# Sheet3.net
KiCad netlist of a schematic drawn in Altium Designer
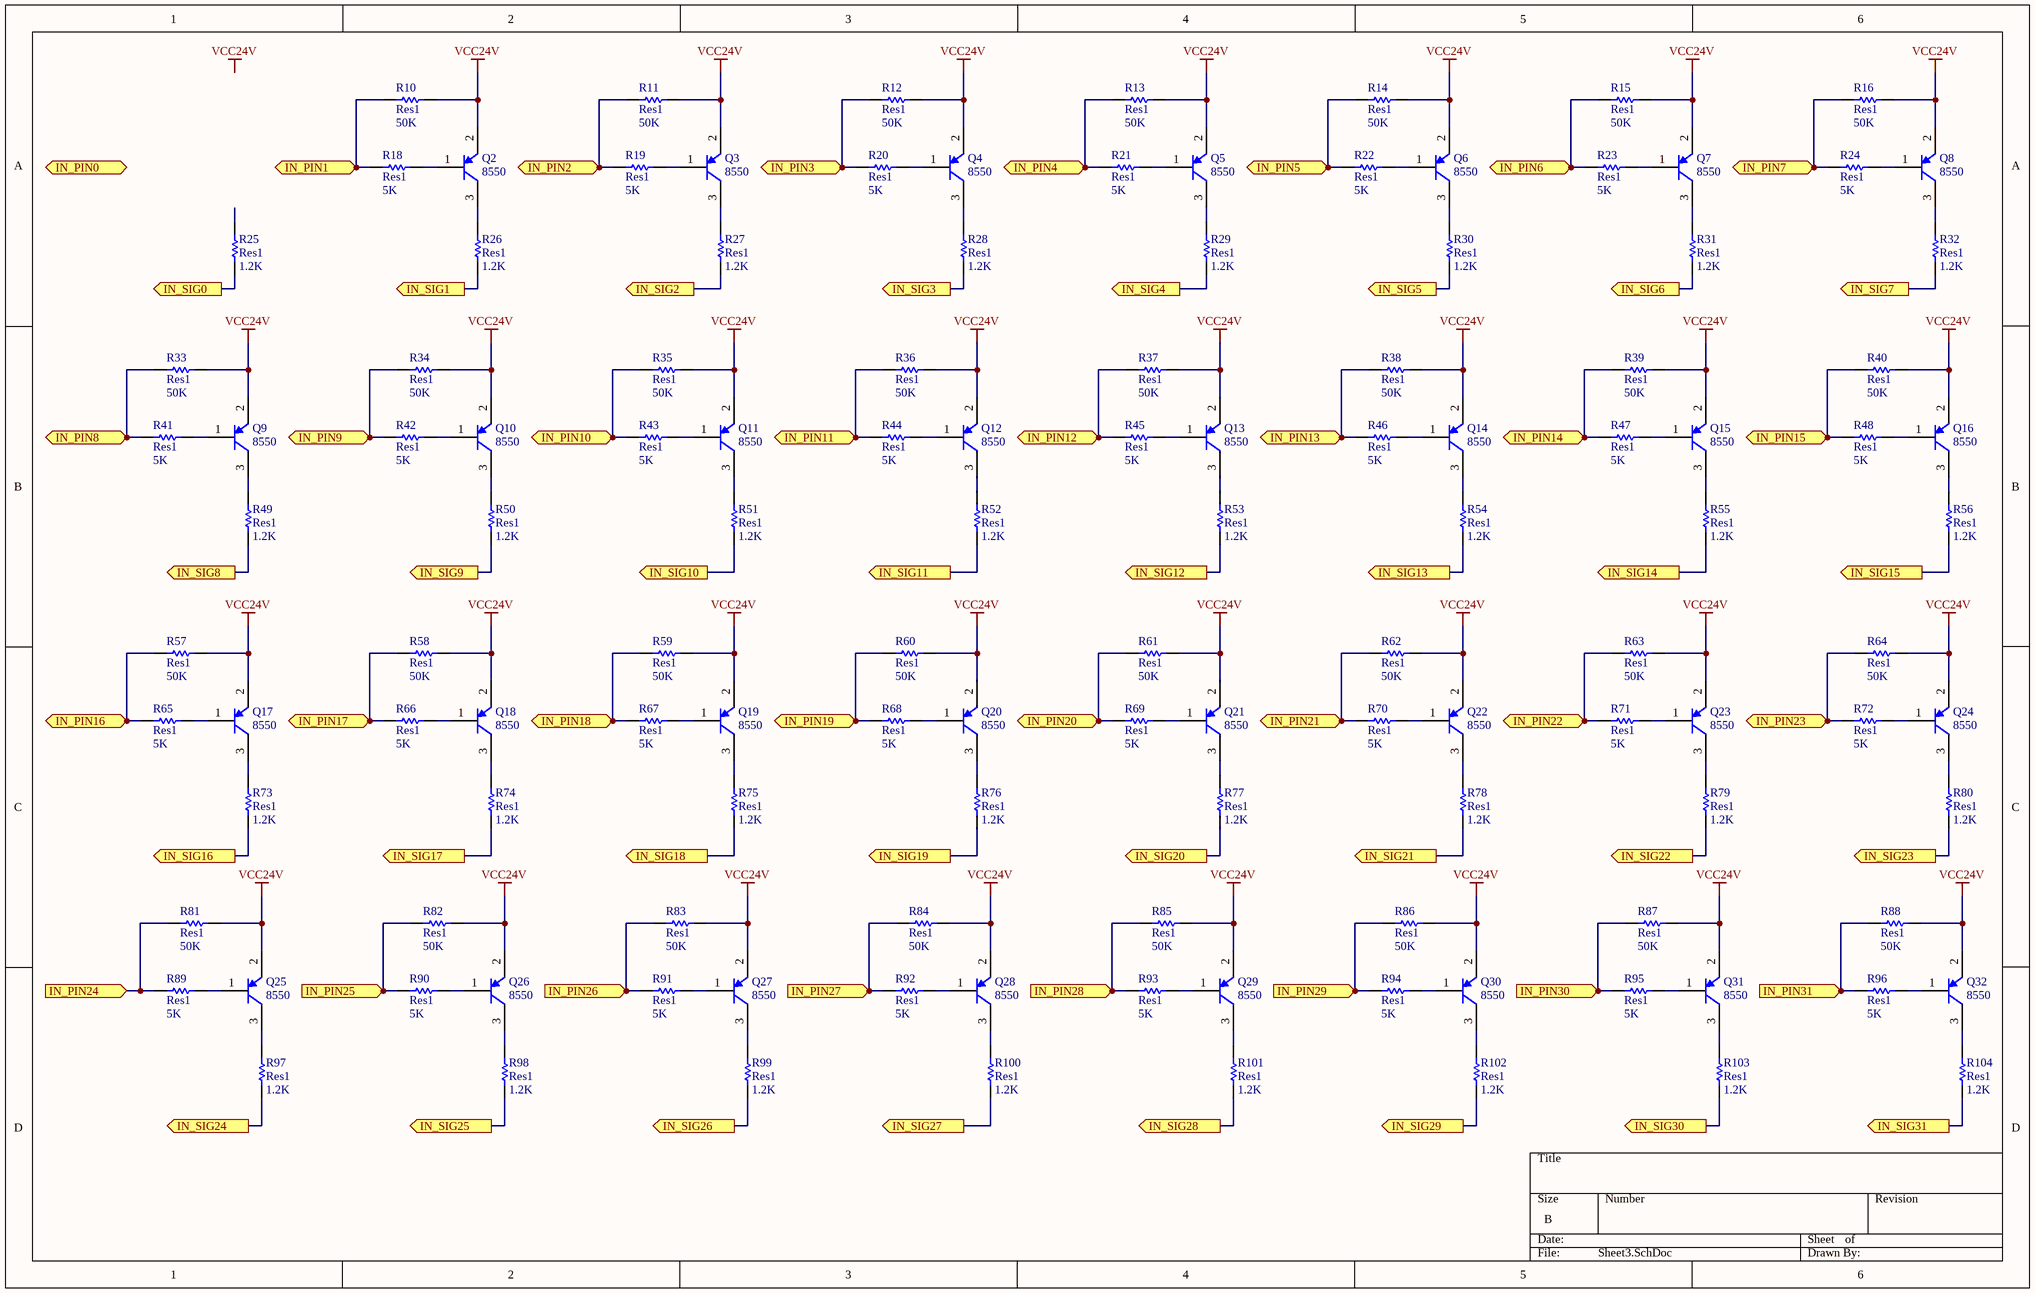
[diagram p0: Sheet3.SchDoc]

(export (version "E")
  (design (tool "Eeschema 10.0.6"))
  (components
    (comp (ref "Q2") (value "8550") (footprint "Sot23-3") (libsource (lib "dolphi_ecs") (part "PNP")))
    (comp (ref "Q3") (value "8550") (footprint "Sot23-3") (libsource (lib "dolphi_ecs") (part "PNP")))
    (comp (ref "Q4") (value "8550") (footprint "Sot23-3") (libsource (lib "dolphi_ecs") (part "PNP")))
    (comp (ref "Q5") (value "8550") (footprint "Sot23-3") (libsource (lib "dolphi_ecs") (part "PNP")))
    (comp (ref "Q6") (value "8550") (footprint "Sot23-3") (libsource (lib "dolphi_ecs") (part "PNP")))
    (comp (ref "Q7") (value "8550") (footprint "Sot23-3") (libsource (lib "dolphi_ecs") (part "PNP")))
    (comp (ref "Q8") (value "8550") (footprint "Sot23-3") (libsource (lib "dolphi_ecs") (part "PNP")))
    (comp (ref "Q9") (value "8550") (footprint "Sot23-3") (libsource (lib "dolphi_ecs") (part "PNP")))
    (comp (ref "Q10") (value "8550") (footprint "Sot23-3") (libsource (lib "dolphi_ecs") (part "PNP")))
    (comp (ref "Q11") (value "8550") (footprint "Sot23-3") (libsource (lib "dolphi_ecs") (part "PNP")))
    (comp (ref "Q12") (value "8550") (footprint "Sot23-3") (libsource (lib "dolphi_ecs") (part "PNP")))
    (comp (ref "Q13") (value "8550") (footprint "Sot23-3") (libsource (lib "dolphi_ecs") (part "PNP")))
    (comp (ref "Q14") (value "8550") (footprint "Sot23-3") (libsource (lib "dolphi_ecs") (part "PNP")))
    (comp (ref "Q15") (value "8550") (footprint "Sot23-3") (libsource (lib "dolphi_ecs") (part "PNP")))
    (comp (ref "Q16") (value "8550") (footprint "Sot23-3") (libsource (lib "dolphi_ecs") (part "PNP")))
    (comp (ref "Q17") (value "8550") (footprint "Sot23-3") (libsource (lib "dolphi_ecs") (part "PNP")))
    (comp (ref "Q18") (value "8550") (footprint "Sot23-3") (libsource (lib "dolphi_ecs") (part "PNP")))
    (comp (ref "Q19") (value "8550") (footprint "Sot23-3") (libsource (lib "dolphi_ecs") (part "PNP")))
    (comp (ref "Q20") (value "8550") (footprint "Sot23-3") (libsource (lib "dolphi_ecs") (part "PNP")))
    (comp (ref "Q21") (value "8550") (footprint "Sot23-3") (libsource (lib "dolphi_ecs") (part "PNP")))
    (comp (ref "Q22") (value "8550") (footprint "Sot23-3") (libsource (lib "dolphi_ecs") (part "PNP")))
    (comp (ref "Q23") (value "8550") (footprint "Sot23-3") (libsource (lib "dolphi_ecs") (part "PNP")))
    (comp (ref "Q24") (value "8550") (footprint "Sot23-3") (libsource (lib "dolphi_ecs") (part "PNP")))
    (comp (ref "Q25") (value "8550") (footprint "Sot23-3") (libsource (lib "dolphi_ecs") (part "PNP")))
    (comp (ref "Q26") (value "8550") (footprint "Sot23-3") (libsource (lib "dolphi_ecs") (part "PNP")))
    (comp (ref "Q27") (value "8550") (footprint "Sot23-3") (libsource (lib "dolphi_ecs") (part "PNP")))
    (comp (ref "Q28") (value "8550") (footprint "Sot23-3") (libsource (lib "dolphi_ecs") (part "PNP")))
    (comp (ref "Q29") (value "8550") (footprint "Sot23-3") (libsource (lib "dolphi_ecs") (part "PNP")))
    (comp (ref "Q30") (value "8550") (footprint "Sot23-3") (libsource (lib "dolphi_ecs") (part "PNP")))
    (comp (ref "Q31") (value "8550") (footprint "Sot23-3") (libsource (lib "dolphi_ecs") (part "PNP")))
    (comp (ref "Q32") (value "8550") (footprint "Sot23-3") (libsource (lib "dolphi_ecs") (part "PNP")))
    (comp (ref "R10")
      (value "Res1")
      (footprint "0805")
      (description "Resistor")
      (fields (field (name "ALTIUM_VALUE") "50K") (field (name "PUBLISHER") "Altium Limited"))
      (libsource (lib "Miscellaneous Devices") (part "Res1"))
    )
    (comp (ref "R11")
      (value "Res1")
      (footprint "0805")
      (description "Resistor")
      (fields (field (name "ALTIUM_VALUE") "50K") (field (name "PUBLISHER") "Altium Limited"))
      (libsource (lib "Miscellaneous Devices") (part "Res1"))
    )
    (comp (ref "R12")
      (value "Res1")
      (footprint "0805")
      (description "Resistor")
      (fields (field (name "ALTIUM_VALUE") "50K") (field (name "PUBLISHER") "Altium Limited"))
      (libsource (lib "Miscellaneous Devices") (part "Res1"))
    )
    (comp (ref "R13")
      (value "Res1")
      (footprint "0805")
      (description "Resistor")
      (fields (field (name "ALTIUM_VALUE") "50K") (field (name "PUBLISHER") "Altium Limited"))
      (libsource (lib "Miscellaneous Devices") (part "Res1"))
    )
    (comp (ref "R14")
      (value "Res1")
      (footprint "0805")
      (description "Resistor")
      (fields (field (name "ALTIUM_VALUE") "50K") (field (name "PUBLISHER") "Altium Limited"))
      (libsource (lib "Miscellaneous Devices") (part "Res1"))
    )
    (comp (ref "R15")
      (value "Res1")
      (footprint "0805")
      (description "Resistor")
      (fields (field (name "ALTIUM_VALUE") "50K") (field (name "PUBLISHER") "Altium Limited"))
      (libsource (lib "Miscellaneous Devices") (part "Res1"))
    )
    (comp (ref "R16")
      (value "Res1")
      (footprint "0805")
      (description "Resistor")
      (fields (field (name "ALTIUM_VALUE") "50K") (field (name "PUBLISHER") "Altium Limited"))
      (libsource (lib "Miscellaneous Devices") (part "Res1"))
    )
    (comp (ref "R18")
      (value "Res1")
      (footprint "0805")
      (description "Resistor")
      (fields (field (name "ALTIUM_VALUE") "5K") (field (name "PUBLISHER") "Altium Limited"))
      (libsource (lib "Miscellaneous Devices") (part "Res1"))
    )
    (comp (ref "R19")
      (value "Res1")
      (footprint "0805")
      (description "Resistor")
      (fields (field (name "ALTIUM_VALUE") "5K") (field (name "PUBLISHER") "Altium Limited"))
      (libsource (lib "Miscellaneous Devices") (part "Res1"))
    )
    (comp (ref "R20")
      (value "Res1")
      (footprint "0805")
      (description "Resistor")
      (fields (field (name "ALTIUM_VALUE") "5K") (field (name "PUBLISHER") "Altium Limited"))
      (libsource (lib "Miscellaneous Devices") (part "Res1"))
    )
    (comp (ref "R21")
      (value "Res1")
      (footprint "0805")
      (description "Resistor")
      (fields (field (name "ALTIUM_VALUE") "5K") (field (name "PUBLISHER") "Altium Limited"))
      (libsource (lib "Miscellaneous Devices") (part "Res1"))
    )
    (comp (ref "R22")
      (value "Res1")
      (footprint "0805")
      (description "Resistor")
      (fields (field (name "ALTIUM_VALUE") "5K") (field (name "PUBLISHER") "Altium Limited"))
      (libsource (lib "Miscellaneous Devices") (part "Res1"))
    )
    (comp (ref "R23")
      (value "Res1")
      (footprint "0805")
      (description "Resistor")
      (fields (field (name "ALTIUM_VALUE") "5K") (field (name "PUBLISHER") "Altium Limited"))
      (libsource (lib "Miscellaneous Devices") (part "Res1"))
    )
    (comp (ref "R24")
      (value "Res1")
      (footprint "0805")
      (description "Resistor")
      (fields (field (name "ALTIUM_VALUE") "5K") (field (name "PUBLISHER") "Altium Limited"))
      (libsource (lib "Miscellaneous Devices") (part "Res1"))
    )
    (comp (ref "R25")
      (value "Res1")
      (footprint "0805")
      (description "Resistor")
      (fields (field (name "ALTIUM_VALUE") "1.2K") (field (name "PUBLISHER") "Altium Limited"))
      (libsource (lib "Miscellaneous Devices") (part "Res1"))
    )
    (comp (ref "R26")
      (value "Res1")
      (footprint "0805")
      (description "Resistor")
      (fields (field (name "ALTIUM_VALUE") "1.2K") (field (name "PUBLISHER") "Altium Limited"))
      (libsource (lib "Miscellaneous Devices") (part "Res1"))
    )
    (comp (ref "R27")
      (value "Res1")
      (footprint "0805")
      (description "Resistor")
      (fields (field (name "ALTIUM_VALUE") "1.2K") (field (name "PUBLISHER") "Altium Limited"))
      (libsource (lib "Miscellaneous Devices") (part "Res1"))
    )
    (comp (ref "R28")
      (value "Res1")
      (footprint "0805")
      (description "Resistor")
      (fields (field (name "ALTIUM_VALUE") "1.2K") (field (name "PUBLISHER") "Altium Limited"))
      (libsource (lib "Miscellaneous Devices") (part "Res1"))
    )
    (comp (ref "R29")
      (value "Res1")
      (footprint "0805")
      (description "Resistor")
      (fields (field (name "ALTIUM_VALUE") "1.2K") (field (name "PUBLISHER") "Altium Limited"))
      (libsource (lib "Miscellaneous Devices") (part "Res1"))
    )
    (comp (ref "R30")
      (value "Res1")
      (footprint "0805")
      (description "Resistor")
      (fields (field (name "ALTIUM_VALUE") "1.2K") (field (name "PUBLISHER") "Altium Limited"))
      (libsource (lib "Miscellaneous Devices") (part "Res1"))
    )
    (comp (ref "R31")
      (value "Res1")
      (footprint "0805")
      (description "Resistor")
      (fields (field (name "ALTIUM_VALUE") "1.2K") (field (name "PUBLISHER") "Altium Limited"))
      (libsource (lib "Miscellaneous Devices") (part "Res1"))
    )
    (comp (ref "R32")
      (value "Res1")
      (footprint "0805")
      (description "Resistor")
      (fields (field (name "ALTIUM_VALUE") "1.2K") (field (name "PUBLISHER") "Altium Limited"))
      (libsource (lib "Miscellaneous Devices") (part "Res1"))
    )
    (comp (ref "R33")
      (value "Res1")
      (footprint "0805")
      (description "Resistor")
      (fields (field (name "ALTIUM_VALUE") "50K") (field (name "PUBLISHER") "Altium Limited"))
      (libsource (lib "Miscellaneous Devices") (part "Res1"))
    )
    (comp (ref "R34")
      (value "Res1")
      (footprint "0805")
      (description "Resistor")
      (fields (field (name "ALTIUM_VALUE") "50K") (field (name "PUBLISHER") "Altium Limited"))
      (libsource (lib "Miscellaneous Devices") (part "Res1"))
    )
    (comp (ref "R35")
      (value "Res1")
      (footprint "0805")
      (description "Resistor")
      (fields (field (name "ALTIUM_VALUE") "50K") (field (name "PUBLISHER") "Altium Limited"))
      (libsource (lib "Miscellaneous Devices") (part "Res1"))
    )
    (comp (ref "R36")
      (value "Res1")
      (footprint "0805")
      (description "Resistor")
      (fields (field (name "ALTIUM_VALUE") "50K") (field (name "PUBLISHER") "Altium Limited"))
      (libsource (lib "Miscellaneous Devices") (part "Res1"))
    )
    (comp (ref "R37")
      (value "Res1")
      (footprint "0805")
      (description "Resistor")
      (fields (field (name "ALTIUM_VALUE") "50K") (field (name "PUBLISHER") "Altium Limited"))
      (libsource (lib "Miscellaneous Devices") (part "Res1"))
    )
    (comp (ref "R38")
      (value "Res1")
      (footprint "0805")
      (description "Resistor")
      (fields (field (name "ALTIUM_VALUE") "50K") (field (name "PUBLISHER") "Altium Limited"))
      (libsource (lib "Miscellaneous Devices") (part "Res1"))
    )
    (comp (ref "R39")
      (value "Res1")
      (footprint "0805")
      (description "Resistor")
      (fields (field (name "ALTIUM_VALUE") "50K") (field (name "PUBLISHER") "Altium Limited"))
      (libsource (lib "Miscellaneous Devices") (part "Res1"))
    )
    (comp (ref "R40")
      (value "Res1")
      (footprint "0805")
      (description "Resistor")
      (fields (field (name "ALTIUM_VALUE") "50K") (field (name "PUBLISHER") "Altium Limited"))
      (libsource (lib "Miscellaneous Devices") (part "Res1"))
    )
    (comp (ref "R41")
      (value "Res1")
      (footprint "0805")
      (description "Resistor")
      (fields (field (name "ALTIUM_VALUE") "5K") (field (name "PUBLISHER") "Altium Limited"))
      (libsource (lib "Miscellaneous Devices") (part "Res1"))
    )
    (comp (ref "R42")
      (value "Res1")
      (footprint "0805")
      (description "Resistor")
      (fields (field (name "ALTIUM_VALUE") "5K") (field (name "PUBLISHER") "Altium Limited"))
      (libsource (lib "Miscellaneous Devices") (part "Res1"))
    )
    (comp (ref "R43")
      (value "Res1")
      (footprint "0805")
      (description "Resistor")
      (fields (field (name "ALTIUM_VALUE") "5K") (field (name "PUBLISHER") "Altium Limited"))
      (libsource (lib "Miscellaneous Devices") (part "Res1"))
    )
    (comp (ref "R44")
      (value "Res1")
      (footprint "0805")
      (description "Resistor")
      (fields (field (name "ALTIUM_VALUE") "5K") (field (name "PUBLISHER") "Altium Limited"))
      (libsource (lib "Miscellaneous Devices") (part "Res1"))
    )
    (comp (ref "R45")
      (value "Res1")
      (footprint "0805")
      (description "Resistor")
      (fields (field (name "ALTIUM_VALUE") "5K") (field (name "PUBLISHER") "Altium Limited"))
      (libsource (lib "Miscellaneous Devices") (part "Res1"))
    )
    (comp (ref "R46")
      (value "Res1")
      (footprint "0805")
      (description "Resistor")
      (fields (field (name "ALTIUM_VALUE") "5K") (field (name "PUBLISHER") "Altium Limited"))
      (libsource (lib "Miscellaneous Devices") (part "Res1"))
    )
    (comp (ref "R47")
      (value "Res1")
      (footprint "0805")
      (description "Resistor")
      (fields (field (name "ALTIUM_VALUE") "5K") (field (name "PUBLISHER") "Altium Limited"))
      (libsource (lib "Miscellaneous Devices") (part "Res1"))
    )
    (comp (ref "R48")
      (value "Res1")
      (footprint "0805")
      (description "Resistor")
      (fields (field (name "ALTIUM_VALUE") "5K") (field (name "PUBLISHER") "Altium Limited"))
      (libsource (lib "Miscellaneous Devices") (part "Res1"))
    )
    (comp (ref "R49")
      (value "Res1")
      (footprint "0805")
      (description "Resistor")
      (fields (field (name "ALTIUM_VALUE") "1.2K") (field (name "PUBLISHER") "Altium Limited"))
      (libsource (lib "Miscellaneous Devices") (part "Res1"))
    )
    (comp (ref "R50")
      (value "Res1")
      (footprint "0805")
      (description "Resistor")
      (fields (field (name "ALTIUM_VALUE") "1.2K") (field (name "PUBLISHER") "Altium Limited"))
      (libsource (lib "Miscellaneous Devices") (part "Res1"))
    )
    (comp (ref "R51")
      (value "Res1")
      (footprint "0805")
      (description "Resistor")
      (fields (field (name "ALTIUM_VALUE") "1.2K") (field (name "PUBLISHER") "Altium Limited"))
      (libsource (lib "Miscellaneous Devices") (part "Res1"))
    )
    (comp (ref "R52")
      (value "Res1")
      (footprint "0805")
      (description "Resistor")
      (fields (field (name "ALTIUM_VALUE") "1.2K") (field (name "PUBLISHER") "Altium Limited"))
      (libsource (lib "Miscellaneous Devices") (part "Res1"))
    )
    (comp (ref "R53")
      (value "Res1")
      (footprint "0805")
      (description "Resistor")
      (fields (field (name "ALTIUM_VALUE") "1.2K") (field (name "PUBLISHER") "Altium Limited"))
      (libsource (lib "Miscellaneous Devices") (part "Res1"))
    )
    (comp (ref "R54")
      (value "Res1")
      (footprint "0805")
      (description "Resistor")
      (fields (field (name "ALTIUM_VALUE") "1.2K") (field (name "PUBLISHER") "Altium Limited"))
      (libsource (lib "Miscellaneous Devices") (part "Res1"))
    )
    (comp (ref "R55")
      (value "Res1")
      (footprint "0805")
      (description "Resistor")
      (fields (field (name "ALTIUM_VALUE") "1.2K") (field (name "PUBLISHER") "Altium Limited"))
      (libsource (lib "Miscellaneous Devices") (part "Res1"))
    )
    (comp (ref "R56")
      (value "Res1")
      (footprint "0805")
      (description "Resistor")
      (fields (field (name "ALTIUM_VALUE") "1.2K") (field (name "PUBLISHER") "Altium Limited"))
      (libsource (lib "Miscellaneous Devices") (part "Res1"))
    )
    (comp (ref "R57")
      (value "Res1")
      (footprint "0805")
      (description "Resistor")
      (fields (field (name "ALTIUM_VALUE") "50K") (field (name "PUBLISHER") "Altium Limited"))
      (libsource (lib "Miscellaneous Devices") (part "Res1"))
    )
    (comp (ref "R58")
      (value "Res1")
      (footprint "0805")
      (description "Resistor")
      (fields (field (name "ALTIUM_VALUE") "50K") (field (name "PUBLISHER") "Altium Limited"))
      (libsource (lib "Miscellaneous Devices") (part "Res1"))
    )
    (comp (ref "R59")
      (value "Res1")
      (footprint "0805")
      (description "Resistor")
      (fields (field (name "ALTIUM_VALUE") "50K") (field (name "PUBLISHER") "Altium Limited"))
      (libsource (lib "Miscellaneous Devices") (part "Res1"))
    )
    (comp (ref "R60")
      (value "Res1")
      (footprint "0805")
      (description "Resistor")
      (fields (field (name "ALTIUM_VALUE") "50K") (field (name "PUBLISHER") "Altium Limited"))
      (libsource (lib "Miscellaneous Devices") (part "Res1"))
    )
    (comp (ref "R61")
      (value "Res1")
      (footprint "0805")
      (description "Resistor")
      (fields (field (name "ALTIUM_VALUE") "50K") (field (name "PUBLISHER") "Altium Limited"))
      (libsource (lib "Miscellaneous Devices") (part "Res1"))
    )
    (comp (ref "R62")
      (value "Res1")
      (footprint "0805")
      (description "Resistor")
      (fields (field (name "ALTIUM_VALUE") "50K") (field (name "PUBLISHER") "Altium Limited"))
      (libsource (lib "Miscellaneous Devices") (part "Res1"))
    )
    (comp (ref "R63")
      (value "Res1")
      (footprint "0805")
      (description "Resistor")
      (fields (field (name "ALTIUM_VALUE") "50K") (field (name "PUBLISHER") "Altium Limited"))
      (libsource (lib "Miscellaneous Devices") (part "Res1"))
    )
    (comp (ref "R64")
      (value "Res1")
      (footprint "0805")
      (description "Resistor")
      (fields (field (name "ALTIUM_VALUE") "50K") (field (name "PUBLISHER") "Altium Limited"))
      (libsource (lib "Miscellaneous Devices") (part "Res1"))
    )
    (comp (ref "R65")
      (value "Res1")
      (footprint "0805")
      (description "Resistor")
      (fields (field (name "ALTIUM_VALUE") "5K") (field (name "PUBLISHER") "Altium Limited"))
      (libsource (lib "Miscellaneous Devices") (part "Res1"))
    )
    (comp (ref "R66")
      (value "Res1")
      (footprint "0805")
      (description "Resistor")
      (fields (field (name "ALTIUM_VALUE") "5K") (field (name "PUBLISHER") "Altium Limited"))
      (libsource (lib "Miscellaneous Devices") (part "Res1"))
    )
    (comp (ref "R67")
      (value "Res1")
      (footprint "0805")
      (description "Resistor")
      (fields (field (name "ALTIUM_VALUE") "5K") (field (name "PUBLISHER") "Altium Limited"))
      (libsource (lib "Miscellaneous Devices") (part "Res1"))
    )
    (comp (ref "R68")
      (value "Res1")
      (footprint "0805")
      (description "Resistor")
      (fields (field (name "ALTIUM_VALUE") "5K") (field (name "PUBLISHER") "Altium Limited"))
      (libsource (lib "Miscellaneous Devices") (part "Res1"))
    )
    (comp (ref "R69")
      (value "Res1")
      (footprint "0805")
      (description "Resistor")
      (fields (field (name "ALTIUM_VALUE") "5K") (field (name "PUBLISHER") "Altium Limited"))
      (libsource (lib "Miscellaneous Devices") (part "Res1"))
    )
    (comp (ref "R70")
      (value "Res1")
      (footprint "0805")
      (description "Resistor")
      (fields (field (name "ALTIUM_VALUE") "5K") (field (name "PUBLISHER") "Altium Limited"))
      (libsource (lib "Miscellaneous Devices") (part "Res1"))
    )
    (comp (ref "R71")
      (value "Res1")
      (footprint "0805")
      (description "Resistor")
      (fields (field (name "ALTIUM_VALUE") "5K") (field (name "PUBLISHER") "Altium Limited"))
      (libsource (lib "Miscellaneous Devices") (part "Res1"))
    )
    (comp (ref "R72")
      (value "Res1")
      (footprint "0805")
      (description "Resistor")
      (fields (field (name "ALTIUM_VALUE") "5K") (field (name "PUBLISHER") "Altium Limited"))
      (libsource (lib "Miscellaneous Devices") (part "Res1"))
    )
    (comp (ref "R73")
      (value "Res1")
      (footprint "0805")
      (description "Resistor")
      (fields (field (name "ALTIUM_VALUE") "1.2K") (field (name "PUBLISHER") "Altium Limited"))
      (libsource (lib "Miscellaneous Devices") (part "Res1"))
    )
    (comp (ref "R74")
      (value "Res1")
      (footprint "0805")
      (description "Resistor")
      (fields (field (name "ALTIUM_VALUE") "1.2K") (field (name "PUBLISHER") "Altium Limited"))
      (libsource (lib "Miscellaneous Devices") (part "Res1"))
    )
    (comp (ref "R75")
      (value "Res1")
      (footprint "0805")
      (description "Resistor")
      (fields (field (name "ALTIUM_VALUE") "1.2K") (field (name "PUBLISHER") "Altium Limited"))
      (libsource (lib "Miscellaneous Devices") (part "Res1"))
    )
    (comp (ref "R76")
      (value "Res1")
      (footprint "0805")
      (description "Resistor")
      (fields (field (name "ALTIUM_VALUE") "1.2K") (field (name "PUBLISHER") "Altium Limited"))
      (libsource (lib "Miscellaneous Devices") (part "Res1"))
    )
    (comp (ref "R77")
      (value "Res1")
      (footprint "0805")
      (description "Resistor")
      (fields (field (name "ALTIUM_VALUE") "1.2K") (field (name "PUBLISHER") "Altium Limited"))
      (libsource (lib "Miscellaneous Devices") (part "Res1"))
    )
    (comp (ref "R78")
      (value "Res1")
      (footprint "0805")
      (description "Resistor")
      (fields (field (name "ALTIUM_VALUE") "1.2K") (field (name "PUBLISHER") "Altium Limited"))
      (libsource (lib "Miscellaneous Devices") (part "Res1"))
    )
    (comp (ref "R79")
      (value "Res1")
      (footprint "0805")
      (description "Resistor")
      (fields (field (name "ALTIUM_VALUE") "1.2K") (field (name "PUBLISHER") "Altium Limited"))
      (libsource (lib "Miscellaneous Devices") (part "Res1"))
    )
    (comp (ref "R80")
      (value "Res1")
      (footprint "0805")
      (description "Resistor")
      (fields (field (name "ALTIUM_VALUE") "1.2K") (field (name "PUBLISHER") "Altium Limited"))
      (libsource (lib "Miscellaneous Devices") (part "Res1"))
    )
    (comp (ref "R81")
      (value "Res1")
      (footprint "0805")
      (description "Resistor")
      (fields (field (name "ALTIUM_VALUE") "50K") (field (name "PUBLISHER") "Altium Limited"))
      (libsource (lib "Miscellaneous Devices") (part "Res1"))
    )
    (comp (ref "R82")
      (value "Res1")
      (footprint "0805")
      (description "Resistor")
      (fields (field (name "ALTIUM_VALUE") "50K") (field (name "PUBLISHER") "Altium Limited"))
      (libsource (lib "Miscellaneous Devices") (part "Res1"))
    )
    (comp (ref "R83")
      (value "Res1")
      (footprint "0805")
      (description "Resistor")
      (fields (field (name "ALTIUM_VALUE") "50K") (field (name "PUBLISHER") "Altium Limited"))
      (libsource (lib "Miscellaneous Devices") (part "Res1"))
    )
    (comp (ref "R84")
      (value "Res1")
      (footprint "0805")
      (description "Resistor")
      (fields (field (name "ALTIUM_VALUE") "50K") (field (name "PUBLISHER") "Altium Limited"))
      (libsource (lib "Miscellaneous Devices") (part "Res1"))
    )
    (comp (ref "R85")
      (value "Res1")
      (footprint "0805")
      (description "Resistor")
      (fields (field (name "ALTIUM_VALUE") "50K") (field (name "PUBLISHER") "Altium Limited"))
      (libsource (lib "Miscellaneous Devices") (part "Res1"))
    )
    (comp (ref "R86")
      (value "Res1")
      (footprint "0805")
      (description "Resistor")
      (fields (field (name "ALTIUM_VALUE") "50K") (field (name "PUBLISHER") "Altium Limited"))
      (libsource (lib "Miscellaneous Devices") (part "Res1"))
    )
    (comp (ref "R87")
      (value "Res1")
      (footprint "0805")
      (description "Resistor")
      (fields (field (name "ALTIUM_VALUE") "50K") (field (name "PUBLISHER") "Altium Limited"))
      (libsource (lib "Miscellaneous Devices") (part "Res1"))
    )
    (comp (ref "R88")
      (value "Res1")
      (footprint "0805")
      (description "Resistor")
      (fields (field (name "ALTIUM_VALUE") "50K") (field (name "PUBLISHER") "Altium Limited"))
      (libsource (lib "Miscellaneous Devices") (part "Res1"))
    )
    (comp (ref "R89")
      (value "Res1")
      (footprint "0805")
      (description "Resistor")
      (fields (field (name "ALTIUM_VALUE") "5K") (field (name "PUBLISHER") "Altium Limited"))
      (libsource (lib "Miscellaneous Devices") (part "Res1"))
    )
    (comp (ref "R90")
      (value "Res1")
      (footprint "0805")
      (description "Resistor")
      (fields (field (name "ALTIUM_VALUE") "5K") (field (name "PUBLISHER") "Altium Limited"))
      (libsource (lib "Miscellaneous Devices") (part "Res1"))
    )
    (comp (ref "R91")
      (value "Res1")
      (footprint "0805")
      (description "Resistor")
      (fields (field (name "ALTIUM_VALUE") "5K") (field (name "PUBLISHER") "Altium Limited"))
      (libsource (lib "Miscellaneous Devices") (part "Res1"))
    )
    (comp (ref "R92")
      (value "Res1")
      (footprint "0805")
      (description "Resistor")
      (fields (field (name "ALTIUM_VALUE") "5K") (field (name "PUBLISHER") "Altium Limited"))
      (libsource (lib "Miscellaneous Devices") (part "Res1"))
    )
    (comp (ref "R93")
      (value "Res1")
      (footprint "0805")
      (description "Resistor")
      (fields (field (name "ALTIUM_VALUE") "5K") (field (name "PUBLISHER") "Altium Limited"))
      (libsource (lib "Miscellaneous Devices") (part "Res1"))
    )
    (comp (ref "R94")
      (value "Res1")
      (footprint "0805")
      (description "Resistor")
      (fields (field (name "ALTIUM_VALUE") "5K") (field (name "PUBLISHER") "Altium Limited"))
      (libsource (lib "Miscellaneous Devices") (part "Res1"))
    )
    (comp (ref "R95")
      (value "Res1")
      (footprint "0805")
      (description "Resistor")
      (fields (field (name "ALTIUM_VALUE") "5K") (field (name "PUBLISHER") "Altium Limited"))
      (libsource (lib "Miscellaneous Devices") (part "Res1"))
    )
    (comp (ref "R96")
      (value "Res1")
      (footprint "0805")
      (description "Resistor")
      (fields (field (name "ALTIUM_VALUE") "5K") (field (name "PUBLISHER") "Altium Limited"))
      (libsource (lib "Miscellaneous Devices") (part "Res1"))
    )
    (comp (ref "R97")
      (value "Res1")
      (footprint "0805")
      (description "Resistor")
      (fields (field (name "ALTIUM_VALUE") "1.2K") (field (name "PUBLISHER") "Altium Limited"))
      (libsource (lib "Miscellaneous Devices") (part "Res1"))
    )
    (comp (ref "R98")
      (value "Res1")
      (footprint "0805")
      (description "Resistor")
      (fields (field (name "ALTIUM_VALUE") "1.2K") (field (name "PUBLISHER") "Altium Limited"))
      (libsource (lib "Miscellaneous Devices") (part "Res1"))
    )
    (comp (ref "R99")
      (value "Res1")
      (footprint "0805")
      (description "Resistor")
      (fields (field (name "ALTIUM_VALUE") "1.2K") (field (name "PUBLISHER") "Altium Limited"))
      (libsource (lib "Miscellaneous Devices") (part "Res1"))
    )
    (comp (ref "R100")
      (value "Res1")
      (footprint "0805")
      (description "Resistor")
      (fields (field (name "ALTIUM_VALUE") "1.2K") (field (name "PUBLISHER") "Altium Limited"))
      (libsource (lib "Miscellaneous Devices") (part "Res1"))
    )
    (comp (ref "R101")
      (value "Res1")
      (footprint "0805")
      (description "Resistor")
      (fields (field (name "ALTIUM_VALUE") "1.2K") (field (name "PUBLISHER") "Altium Limited"))
      (libsource (lib "Miscellaneous Devices") (part "Res1"))
    )
    (comp (ref "R102")
      (value "Res1")
      (footprint "0805")
      (description "Resistor")
      (fields (field (name "ALTIUM_VALUE") "1.2K") (field (name "PUBLISHER") "Altium Limited"))
      (libsource (lib "Miscellaneous Devices") (part "Res1"))
    )
    (comp (ref "R103")
      (value "Res1")
      (footprint "0805")
      (description "Resistor")
      (fields (field (name "ALTIUM_VALUE") "1.2K") (field (name "PUBLISHER") "Altium Limited"))
      (libsource (lib "Miscellaneous Devices") (part "Res1"))
    )
    (comp (ref "R104")
      (value "Res1")
      (footprint "0805")
      (description "Resistor")
      (fields (field (name "ALTIUM_VALUE") "1.2K") (field (name "PUBLISHER") "Altium Limited"))
      (libsource (lib "Miscellaneous Devices") (part "Res1"))
    )
  )
  (nets
    (net (code "2") (name "/IN_PIN1") (class "Default")
      (node (ref "R10") (pin "2") (pinfunction "2_2") (pintype "passive"))
      (node (ref "R18") (pin "1") (pinfunction "1_1") (pintype "passive"))
    )
    (net (code "3") (name "/IN_PIN2") (class "Default")
      (node (ref "R11") (pin "2") (pinfunction "2_2") (pintype "passive"))
      (node (ref "R19") (pin "1") (pinfunction "1_1") (pintype "passive"))
    )
    (net (code "4") (name "/IN_PIN3") (class "Default")
      (node (ref "R12") (pin "2") (pinfunction "2_2") (pintype "passive"))
      (node (ref "R20") (pin "1") (pinfunction "1_1") (pintype "passive"))
    )
    (net (code "5") (name "/IN_PIN4") (class "Default")
      (node (ref "R13") (pin "2") (pinfunction "2_2") (pintype "passive"))
      (node (ref "R21") (pin "1") (pinfunction "1_1") (pintype "passive"))
    )
    (net (code "6") (name "/IN_PIN5") (class "Default")
      (node (ref "R14") (pin "2") (pinfunction "2_2") (pintype "passive"))
      (node (ref "R22") (pin "1") (pinfunction "1_1") (pintype "passive"))
    )
    (net (code "7") (name "/IN_PIN6") (class "Default")
      (node (ref "R15") (pin "2") (pinfunction "2_2") (pintype "passive"))
      (node (ref "R23") (pin "1") (pinfunction "1_1") (pintype "passive"))
    )
    (net (code "8") (name "/IN_PIN7") (class "Default")
      (node (ref "R16") (pin "2") (pinfunction "2_2") (pintype "passive"))
      (node (ref "R24") (pin "1") (pinfunction "1_1") (pintype "passive"))
    )
    (net (code "9") (name "/IN_PIN8") (class "Default")
      (node (ref "R33") (pin "2") (pinfunction "2_2") (pintype "passive"))
      (node (ref "R41") (pin "1") (pinfunction "1_1") (pintype "passive"))
    )
    (net (code "10") (name "/IN_PIN9") (class "Default")
      (node (ref "R34") (pin "2") (pinfunction "2_2") (pintype "passive"))
      (node (ref "R42") (pin "1") (pinfunction "1_1") (pintype "passive"))
    )
    (net (code "11") (name "/IN_PIN10") (class "Default")
      (node (ref "R35") (pin "2") (pinfunction "2_2") (pintype "passive"))
      (node (ref "R43") (pin "1") (pinfunction "1_1") (pintype "passive"))
    )
    (net (code "12") (name "/IN_PIN11") (class "Default")
      (node (ref "R36") (pin "2") (pinfunction "2_2") (pintype "passive"))
      (node (ref "R44") (pin "1") (pinfunction "1_1") (pintype "passive"))
    )
    (net (code "13") (name "/IN_PIN12") (class "Default")
      (node (ref "R37") (pin "2") (pinfunction "2_2") (pintype "passive"))
      (node (ref "R45") (pin "1") (pinfunction "1_1") (pintype "passive"))
    )
    (net (code "14") (name "/IN_PIN13") (class "Default")
      (node (ref "R38") (pin "2") (pinfunction "2_2") (pintype "passive"))
      (node (ref "R46") (pin "1") (pinfunction "1_1") (pintype "passive"))
    )
    (net (code "15") (name "/IN_PIN14") (class "Default")
      (node (ref "R39") (pin "2") (pinfunction "2_2") (pintype "passive"))
      (node (ref "R47") (pin "1") (pinfunction "1_1") (pintype "passive"))
    )
    (net (code "16") (name "/IN_PIN15") (class "Default")
      (node (ref "R40") (pin "2") (pinfunction "2_2") (pintype "passive"))
      (node (ref "R48") (pin "1") (pinfunction "1_1") (pintype "passive"))
    )
    (net (code "17") (name "/IN_PIN16") (class "Default")
      (node (ref "R57") (pin "2") (pinfunction "2_2") (pintype "passive"))
      (node (ref "R65") (pin "1") (pinfunction "1_1") (pintype "passive"))
    )
    (net (code "18") (name "/IN_PIN17") (class "Default")
      (node (ref "R58") (pin "2") (pinfunction "2_2") (pintype "passive"))
      (node (ref "R66") (pin "1") (pinfunction "1_1") (pintype "passive"))
    )
    (net (code "19") (name "/IN_PIN18") (class "Default")
      (node (ref "R59") (pin "2") (pinfunction "2_2") (pintype "passive"))
      (node (ref "R67") (pin "1") (pinfunction "1_1") (pintype "passive"))
    )
    (net (code "20") (name "/IN_PIN19") (class "Default")
      (node (ref "R60") (pin "2") (pinfunction "2_2") (pintype "passive"))
      (node (ref "R68") (pin "1") (pinfunction "1_1") (pintype "passive"))
    )
    (net (code "21") (name "/IN_PIN20") (class "Default")
      (node (ref "R61") (pin "2") (pinfunction "2_2") (pintype "passive"))
      (node (ref "R69") (pin "1") (pinfunction "1_1") (pintype "passive"))
    )
    (net (code "22") (name "/IN_PIN21") (class "Default")
      (node (ref "R62") (pin "2") (pinfunction "2_2") (pintype "passive"))
      (node (ref "R70") (pin "1") (pinfunction "1_1") (pintype "passive"))
    )
    (net (code "23") (name "/IN_PIN22") (class "Default")
      (node (ref "R63") (pin "2") (pinfunction "2_2") (pintype "passive"))
      (node (ref "R71") (pin "1") (pinfunction "1_1") (pintype "passive"))
    )
    (net (code "24") (name "/IN_PIN23") (class "Default")
      (node (ref "R64") (pin "2") (pinfunction "2_2") (pintype "passive"))
      (node (ref "R72") (pin "1") (pinfunction "1_1") (pintype "passive"))
    )
    (net (code "25") (name "/IN_PIN24") (class "Default")
      (node (ref "R81") (pin "2") (pinfunction "2_2") (pintype "passive"))
      (node (ref "R89") (pin "1") (pinfunction "1_1") (pintype "passive"))
    )
    (net (code "26") (name "/IN_PIN25") (class "Default")
      (node (ref "R82") (pin "2") (pinfunction "2_2") (pintype "passive"))
      (node (ref "R90") (pin "1") (pinfunction "1_1") (pintype "passive"))
    )
    (net (code "27") (name "/IN_PIN26") (class "Default")
      (node (ref "R83") (pin "2") (pinfunction "2_2") (pintype "passive"))
      (node (ref "R91") (pin "1") (pinfunction "1_1") (pintype "passive"))
    )
    (net (code "28") (name "/IN_PIN27") (class "Default")
      (node (ref "R84") (pin "2") (pinfunction "2_2") (pintype "passive"))
      (node (ref "R92") (pin "1") (pinfunction "1_1") (pintype "passive"))
    )
    (net (code "29") (name "/IN_PIN28") (class "Default")
      (node (ref "R85") (pin "2") (pinfunction "2_2") (pintype "passive"))
      (node (ref "R93") (pin "1") (pinfunction "1_1") (pintype "passive"))
    )
    (net (code "30") (name "/IN_PIN29") (class "Default")
      (node (ref "R86") (pin "2") (pinfunction "2_2") (pintype "passive"))
      (node (ref "R94") (pin "1") (pinfunction "1_1") (pintype "passive"))
    )
    (net (code "31") (name "/IN_PIN30") (class "Default")
      (node (ref "R87") (pin "2") (pinfunction "2_2") (pintype "passive"))
      (node (ref "R95") (pin "1") (pinfunction "1_1") (pintype "passive"))
    )
    (net (code "32") (name "/IN_PIN31") (class "Default")
      (node (ref "R88") (pin "2") (pinfunction "2_2") (pintype "passive"))
      (node (ref "R96") (pin "1") (pinfunction "1_1") (pintype "passive"))
    )
    (net (code "33") (name "/IN_SIG0") (class "Default")
      (node (ref "R25") (pin "2") (pinfunction "2_2") (pintype "passive"))
    )
    (net (code "34") (name "/IN_SIG1") (class "Default")
      (node (ref "R26") (pin "2") (pinfunction "2_2") (pintype "passive"))
    )
    (net (code "35") (name "/IN_SIG2") (class "Default")
      (node (ref "R27") (pin "2") (pinfunction "2_2") (pintype "passive"))
    )
    (net (code "36") (name "/IN_SIG3") (class "Default")
      (node (ref "R28") (pin "2") (pinfunction "2_2") (pintype "passive"))
    )
    (net (code "37") (name "/IN_SIG4") (class "Default")
      (node (ref "R29") (pin "2") (pinfunction "2_2") (pintype "passive"))
    )
    (net (code "38") (name "/IN_SIG5") (class "Default")
      (node (ref "R30") (pin "2") (pinfunction "2_2") (pintype "passive"))
    )
    (net (code "39") (name "/IN_SIG6") (class "Default")
      (node (ref "R31") (pin "2") (pinfunction "2_2") (pintype "passive"))
    )
    (net (code "40") (name "/IN_SIG7") (class "Default")
      (node (ref "R32") (pin "2") (pinfunction "2_2") (pintype "passive"))
    )
    (net (code "41") (name "/IN_SIG8") (class "Default")
      (node (ref "R49") (pin "2") (pinfunction "2_2") (pintype "passive"))
    )
    (net (code "42") (name "/IN_SIG9") (class "Default")
      (node (ref "R50") (pin "2") (pinfunction "2_2") (pintype "passive"))
    )
    (net (code "43") (name "/IN_SIG10") (class "Default")
      (node (ref "R51") (pin "2") (pinfunction "2_2") (pintype "passive"))
    )
    (net (code "44") (name "/IN_SIG11") (class "Default")
      (node (ref "R52") (pin "2") (pinfunction "2_2") (pintype "passive"))
    )
    (net (code "45") (name "/IN_SIG12") (class "Default")
      (node (ref "R53") (pin "2") (pinfunction "2_2") (pintype "passive"))
    )
    (net (code "46") (name "/IN_SIG13") (class "Default")
      (node (ref "R54") (pin "2") (pinfunction "2_2") (pintype "passive"))
    )
    (net (code "47") (name "/IN_SIG14") (class "Default")
      (node (ref "R55") (pin "2") (pinfunction "2_2") (pintype "passive"))
    )
    (net (code "48") (name "/IN_SIG15") (class "Default")
      (node (ref "R56") (pin "2") (pinfunction "2_2") (pintype "passive"))
    )
    (net (code "49") (name "/IN_SIG16") (class "Default")
      (node (ref "R73") (pin "2") (pinfunction "2_2") (pintype "passive"))
    )
    (net (code "50") (name "/IN_SIG17") (class "Default")
      (node (ref "R74") (pin "2") (pinfunction "2_2") (pintype "passive"))
    )
    (net (code "51") (name "/IN_SIG18") (class "Default")
      (node (ref "R75") (pin "2") (pinfunction "2_2") (pintype "passive"))
    )
    (net (code "52") (name "/IN_SIG19") (class "Default")
      (node (ref "R76") (pin "2") (pinfunction "2_2") (pintype "passive"))
    )
    (net (code "53") (name "/IN_SIG20") (class "Default")
      (node (ref "R77") (pin "2") (pinfunction "2_2") (pintype "passive"))
    )
    (net (code "54") (name "/IN_SIG21") (class "Default")
      (node (ref "R78") (pin "2") (pinfunction "2_2") (pintype "passive"))
    )
    (net (code "55") (name "/IN_SIG22") (class "Default")
      (node (ref "R79") (pin "2") (pinfunction "2_2") (pintype "passive"))
    )
    (net (code "56") (name "/IN_SIG23") (class "Default")
      (node (ref "R80") (pin "2") (pinfunction "2_2") (pintype "passive"))
    )
    (net (code "57") (name "/IN_SIG24") (class "Default")
      (node (ref "R97") (pin "2") (pinfunction "2_2") (pintype "passive"))
    )
    (net (code "58") (name "/IN_SIG25") (class "Default")
      (node (ref "R98") (pin "2") (pinfunction "2_2") (pintype "passive"))
    )
    (net (code "59") (name "/IN_SIG26") (class "Default")
      (node (ref "R99") (pin "2") (pinfunction "2_2") (pintype "passive"))
    )
    (net (code "60") (name "/IN_SIG27") (class "Default")
      (node (ref "R100") (pin "2") (pinfunction "2_2") (pintype "passive"))
    )
    (net (code "61") (name "/IN_SIG28") (class "Default")
      (node (ref "R101") (pin "2") (pinfunction "2_2") (pintype "passive"))
    )
    (net (code "62") (name "/IN_SIG29") (class "Default")
      (node (ref "R102") (pin "2") (pinfunction "2_2") (pintype "passive"))
    )
    (net (code "63") (name "/IN_SIG30") (class "Default")
      (node (ref "R103") (pin "2") (pinfunction "2_2") (pintype "passive"))
    )
    (net (code "64") (name "/IN_SIG31") (class "Default")
      (node (ref "R104") (pin "2") (pinfunction "2_2") (pintype "passive"))
    )
    (net (code "65") (name "Net-(Q2-B)") (class "Default")
      (node (ref "Q2") (pin "1") (pinfunction "B_1") (pintype "passive"))
      (node (ref "R18") (pin "2") (pinfunction "2_2") (pintype "passive"))
    )
    (net (code "66") (name "Net-(Q2-C)") (class "Default")
      (node (ref "Q2") (pin "3") (pinfunction "C_3") (pintype "passive"))
      (node (ref "R26") (pin "1") (pinfunction "1_1") (pintype "passive"))
    )
    (net (code "67") (name "Net-(Q3-B)") (class "Default")
      (node (ref "Q3") (pin "1") (pinfunction "B_1") (pintype "passive"))
      (node (ref "R19") (pin "2") (pinfunction "2_2") (pintype "passive"))
    )
    (net (code "68") (name "Net-(Q3-C)") (class "Default")
      (node (ref "Q3") (pin "3") (pinfunction "C_3") (pintype "passive"))
      (node (ref "R27") (pin "1") (pinfunction "1_1") (pintype "passive"))
    )
    (net (code "69") (name "Net-(Q4-B)") (class "Default")
      (node (ref "Q4") (pin "1") (pinfunction "B_1") (pintype "passive"))
      (node (ref "R20") (pin "2") (pinfunction "2_2") (pintype "passive"))
    )
    (net (code "70") (name "Net-(Q4-C)") (class "Default")
      (node (ref "Q4") (pin "3") (pinfunction "C_3") (pintype "passive"))
      (node (ref "R28") (pin "1") (pinfunction "1_1") (pintype "passive"))
    )
    (net (code "71") (name "Net-(Q5-B)") (class "Default")
      (node (ref "Q5") (pin "1") (pinfunction "B_1") (pintype "passive"))
      (node (ref "R21") (pin "2") (pinfunction "2_2") (pintype "passive"))
    )
    (net (code "72") (name "Net-(Q5-C)") (class "Default")
      (node (ref "Q5") (pin "3") (pinfunction "C_3") (pintype "passive"))
      (node (ref "R29") (pin "1") (pinfunction "1_1") (pintype "passive"))
    )
    (net (code "73") (name "Net-(Q6-B)") (class "Default")
      (node (ref "Q6") (pin "1") (pinfunction "B_1") (pintype "passive"))
      (node (ref "R22") (pin "2") (pinfunction "2_2") (pintype "passive"))
    )
    (net (code "74") (name "Net-(Q6-C)") (class "Default")
      (node (ref "Q6") (pin "3") (pinfunction "C_3") (pintype "passive"))
      (node (ref "R30") (pin "1") (pinfunction "1_1") (pintype "passive"))
    )
    (net (code "75") (name "Net-(Q7-B)") (class "Default")
      (node (ref "Q7") (pin "1") (pinfunction "B_1") (pintype "passive"))
      (node (ref "R23") (pin "2") (pinfunction "2_2") (pintype "passive"))
    )
    (net (code "76") (name "Net-(Q7-C)") (class "Default")
      (node (ref "Q7") (pin "3") (pinfunction "C_3") (pintype "passive"))
      (node (ref "R31") (pin "1") (pinfunction "1_1") (pintype "passive"))
    )
    (net (code "77") (name "Net-(Q8-B)") (class "Default")
      (node (ref "Q8") (pin "1") (pinfunction "B_1") (pintype "passive"))
      (node (ref "R24") (pin "2") (pinfunction "2_2") (pintype "passive"))
    )
    (net (code "78") (name "Net-(Q8-C)") (class "Default")
      (node (ref "Q8") (pin "3") (pinfunction "C_3") (pintype "passive"))
      (node (ref "R32") (pin "1") (pinfunction "1_1") (pintype "passive"))
    )
    (net (code "79") (name "Net-(Q9-B)") (class "Default")
      (node (ref "Q9") (pin "1") (pinfunction "B_1") (pintype "passive"))
      (node (ref "R41") (pin "2") (pinfunction "2_2") (pintype "passive"))
    )
    (net (code "80") (name "Net-(Q9-C)") (class "Default")
      (node (ref "Q9") (pin "3") (pinfunction "C_3") (pintype "passive"))
      (node (ref "R49") (pin "1") (pinfunction "1_1") (pintype "passive"))
    )
    (net (code "81") (name "Net-(Q10-B)") (class "Default")
      (node (ref "Q10") (pin "1") (pinfunction "B_1") (pintype "passive"))
      (node (ref "R42") (pin "2") (pinfunction "2_2") (pintype "passive"))
    )
    (net (code "82") (name "Net-(Q10-C)") (class "Default")
      (node (ref "Q10") (pin "3") (pinfunction "C_3") (pintype "passive"))
      (node (ref "R50") (pin "1") (pinfunction "1_1") (pintype "passive"))
    )
    (net (code "83") (name "Net-(Q11-B)") (class "Default")
      (node (ref "Q11") (pin "1") (pinfunction "B_1") (pintype "passive"))
      (node (ref "R43") (pin "2") (pinfunction "2_2") (pintype "passive"))
    )
    (net (code "84") (name "Net-(Q11-C)") (class "Default")
      (node (ref "Q11") (pin "3") (pinfunction "C_3") (pintype "passive"))
      (node (ref "R51") (pin "1") (pinfunction "1_1") (pintype "passive"))
    )
    (net (code "85") (name "Net-(Q12-B)") (class "Default")
      (node (ref "Q12") (pin "1") (pinfunction "B_1") (pintype "passive"))
      (node (ref "R44") (pin "2") (pinfunction "2_2") (pintype "passive"))
    )
    (net (code "86") (name "Net-(Q12-C)") (class "Default")
      (node (ref "Q12") (pin "3") (pinfunction "C_3") (pintype "passive"))
      (node (ref "R52") (pin "1") (pinfunction "1_1") (pintype "passive"))
    )
    (net (code "87") (name "Net-(Q13-B)") (class "Default")
      (node (ref "Q13") (pin "1") (pinfunction "B_1") (pintype "passive"))
      (node (ref "R45") (pin "2") (pinfunction "2_2") (pintype "passive"))
    )
    (net (code "88") (name "Net-(Q13-C)") (class "Default")
      (node (ref "Q13") (pin "3") (pinfunction "C_3") (pintype "passive"))
      (node (ref "R53") (pin "1") (pinfunction "1_1") (pintype "passive"))
    )
    (net (code "89") (name "Net-(Q14-B)") (class "Default")
      (node (ref "Q14") (pin "1") (pinfunction "B_1") (pintype "passive"))
      (node (ref "R46") (pin "2") (pinfunction "2_2") (pintype "passive"))
    )
    (net (code "90") (name "Net-(Q14-C)") (class "Default")
      (node (ref "Q14") (pin "3") (pinfunction "C_3") (pintype "passive"))
      (node (ref "R54") (pin "1") (pinfunction "1_1") (pintype "passive"))
    )
    (net (code "91") (name "Net-(Q15-B)") (class "Default")
      (node (ref "Q15") (pin "1") (pinfunction "B_1") (pintype "passive"))
      (node (ref "R47") (pin "2") (pinfunction "2_2") (pintype "passive"))
    )
    (net (code "92") (name "Net-(Q15-C)") (class "Default")
      (node (ref "Q15") (pin "3") (pinfunction "C_3") (pintype "passive"))
      (node (ref "R55") (pin "1") (pinfunction "1_1") (pintype "passive"))
    )
    (net (code "93") (name "Net-(Q16-B)") (class "Default")
      (node (ref "Q16") (pin "1") (pinfunction "B_1") (pintype "passive"))
      (node (ref "R48") (pin "2") (pinfunction "2_2") (pintype "passive"))
    )
    (net (code "94") (name "Net-(Q16-C)") (class "Default")
      (node (ref "Q16") (pin "3") (pinfunction "C_3") (pintype "passive"))
      (node (ref "R56") (pin "1") (pinfunction "1_1") (pintype "passive"))
    )
    (net (code "95") (name "Net-(Q17-B)") (class "Default")
      (node (ref "Q17") (pin "1") (pinfunction "B_1") (pintype "passive"))
      (node (ref "R65") (pin "2") (pinfunction "2_2") (pintype "passive"))
    )
    (net (code "96") (name "Net-(Q17-C)") (class "Default")
      (node (ref "Q17") (pin "3") (pinfunction "C_3") (pintype "passive"))
      (node (ref "R73") (pin "1") (pinfunction "1_1") (pintype "passive"))
    )
    (net (code "97") (name "Net-(Q18-B)") (class "Default")
      (node (ref "Q18") (pin "1") (pinfunction "B_1") (pintype "passive"))
      (node (ref "R66") (pin "2") (pinfunction "2_2") (pintype "passive"))
    )
    (net (code "98") (name "Net-(Q18-C)") (class "Default")
      (node (ref "Q18") (pin "3") (pinfunction "C_3") (pintype "passive"))
      (node (ref "R74") (pin "1") (pinfunction "1_1") (pintype "passive"))
    )
    (net (code "99") (name "Net-(Q19-B)") (class "Default")
      (node (ref "Q19") (pin "1") (pinfunction "B_1") (pintype "passive"))
      (node (ref "R67") (pin "2") (pinfunction "2_2") (pintype "passive"))
    )
    (net (code "100") (name "Net-(Q19-C)") (class "Default")
      (node (ref "Q19") (pin "3") (pinfunction "C_3") (pintype "passive"))
      (node (ref "R75") (pin "1") (pinfunction "1_1") (pintype "passive"))
    )
    (net (code "101") (name "Net-(Q20-B)") (class "Default")
      (node (ref "Q20") (pin "1") (pinfunction "B_1") (pintype "passive"))
      (node (ref "R68") (pin "2") (pinfunction "2_2") (pintype "passive"))
    )
    (net (code "102") (name "Net-(Q20-C)") (class "Default")
      (node (ref "Q20") (pin "3") (pinfunction "C_3") (pintype "passive"))
      (node (ref "R76") (pin "1") (pinfunction "1_1") (pintype "passive"))
    )
    (net (code "103") (name "Net-(Q21-B)") (class "Default")
      (node (ref "Q21") (pin "1") (pinfunction "B_1") (pintype "passive"))
      (node (ref "R69") (pin "2") (pinfunction "2_2") (pintype "passive"))
    )
    (net (code "104") (name "Net-(Q21-C)") (class "Default")
      (node (ref "Q21") (pin "3") (pinfunction "C_3") (pintype "passive"))
      (node (ref "R77") (pin "1") (pinfunction "1_1") (pintype "passive"))
    )
    (net (code "105") (name "Net-(Q22-B)") (class "Default")
      (node (ref "Q22") (pin "1") (pinfunction "B_1") (pintype "passive"))
      (node (ref "R70") (pin "2") (pinfunction "2_2") (pintype "passive"))
    )
    (net (code "106") (name "Net-(Q22-C)") (class "Default")
      (node (ref "Q22") (pin "3") (pinfunction "C_3") (pintype "passive"))
      (node (ref "R78") (pin "1") (pinfunction "1_1") (pintype "passive"))
    )
    (net (code "107") (name "Net-(Q23-B)") (class "Default")
      (node (ref "Q23") (pin "1") (pinfunction "B_1") (pintype "passive"))
      (node (ref "R71") (pin "2") (pinfunction "2_2") (pintype "passive"))
    )
    (net (code "108") (name "Net-(Q23-C)") (class "Default")
      (node (ref "Q23") (pin "3") (pinfunction "C_3") (pintype "passive"))
      (node (ref "R79") (pin "1") (pinfunction "1_1") (pintype "passive"))
    )
    (net (code "109") (name "Net-(Q24-B)") (class "Default")
      (node (ref "Q24") (pin "1") (pinfunction "B_1") (pintype "passive"))
      (node (ref "R72") (pin "2") (pinfunction "2_2") (pintype "passive"))
    )
    (net (code "110") (name "Net-(Q24-C)") (class "Default")
      (node (ref "Q24") (pin "3") (pinfunction "C_3") (pintype "passive"))
      (node (ref "R80") (pin "1") (pinfunction "1_1") (pintype "passive"))
    )
    (net (code "111") (name "Net-(Q25-B)") (class "Default")
      (node (ref "Q25") (pin "1") (pinfunction "B_1") (pintype "passive"))
      (node (ref "R89") (pin "2") (pinfunction "2_2") (pintype "passive"))
    )
    (net (code "112") (name "Net-(Q25-C)") (class "Default")
      (node (ref "Q25") (pin "3") (pinfunction "C_3") (pintype "passive"))
      (node (ref "R97") (pin "1") (pinfunction "1_1") (pintype "passive"))
    )
    (net (code "113") (name "Net-(Q26-B)") (class "Default")
      (node (ref "Q26") (pin "1") (pinfunction "B_1") (pintype "passive"))
      (node (ref "R90") (pin "2") (pinfunction "2_2") (pintype "passive"))
    )
    (net (code "114") (name "Net-(Q26-C)") (class "Default")
      (node (ref "Q26") (pin "3") (pinfunction "C_3") (pintype "passive"))
      (node (ref "R98") (pin "1") (pinfunction "1_1") (pintype "passive"))
    )
    (net (code "115") (name "Net-(Q27-B)") (class "Default")
      (node (ref "Q27") (pin "1") (pinfunction "B_1") (pintype "passive"))
      (node (ref "R91") (pin "2") (pinfunction "2_2") (pintype "passive"))
    )
    (net (code "116") (name "Net-(Q27-C)") (class "Default")
      (node (ref "Q27") (pin "3") (pinfunction "C_3") (pintype "passive"))
      (node (ref "R99") (pin "1") (pinfunction "1_1") (pintype "passive"))
    )
    (net (code "117") (name "Net-(Q28-B)") (class "Default")
      (node (ref "Q28") (pin "1") (pinfunction "B_1") (pintype "passive"))
      (node (ref "R92") (pin "2") (pinfunction "2_2") (pintype "passive"))
    )
    (net (code "118") (name "Net-(Q28-C)") (class "Default")
      (node (ref "Q28") (pin "3") (pinfunction "C_3") (pintype "passive"))
      (node (ref "R100") (pin "1") (pinfunction "1_1") (pintype "passive"))
    )
    (net (code "119") (name "Net-(Q29-B)") (class "Default")
      (node (ref "Q29") (pin "1") (pinfunction "B_1") (pintype "passive"))
      (node (ref "R93") (pin "2") (pinfunction "2_2") (pintype "passive"))
    )
    (net (code "120") (name "Net-(Q29-C)") (class "Default")
      (node (ref "Q29") (pin "3") (pinfunction "C_3") (pintype "passive"))
      (node (ref "R101") (pin "1") (pinfunction "1_1") (pintype "passive"))
    )
    (net (code "121") (name "Net-(Q30-B)") (class "Default")
      (node (ref "Q30") (pin "1") (pinfunction "B_1") (pintype "passive"))
      (node (ref "R94") (pin "2") (pinfunction "2_2") (pintype "passive"))
    )
    (net (code "122") (name "Net-(Q30-C)") (class "Default")
      (node (ref "Q30") (pin "3") (pinfunction "C_3") (pintype "passive"))
      (node (ref "R102") (pin "1") (pinfunction "1_1") (pintype "passive"))
    )
    (net (code "123") (name "Net-(Q31-B)") (class "Default")
      (node (ref "Q31") (pin "1") (pinfunction "B_1") (pintype "passive"))
      (node (ref "R95") (pin "2") (pinfunction "2_2") (pintype "passive"))
    )
    (net (code "124") (name "Net-(Q31-C)") (class "Default")
      (node (ref "Q31") (pin "3") (pinfunction "C_3") (pintype "passive"))
      (node (ref "R103") (pin "1") (pinfunction "1_1") (pintype "passive"))
    )
    (net (code "125") (name "Net-(Q32-B)") (class "Default")
      (node (ref "Q32") (pin "1") (pinfunction "B_1") (pintype "passive"))
      (node (ref "R96") (pin "2") (pinfunction "2_2") (pintype "passive"))
    )
    (net (code "126") (name "Net-(Q32-C)") (class "Default")
      (node (ref "Q32") (pin "3") (pinfunction "C_3") (pintype "passive"))
      (node (ref "R104") (pin "1") (pinfunction "1_1") (pintype "passive"))
    )
    (net (code "127") (name "VCC24V") (class "Default")
      (node (ref "Q10") (pin "2") (pinfunction "E_2") (pintype "passive"))
      (node (ref "Q11") (pin "2") (pinfunction "E_2") (pintype "passive"))
      (node (ref "Q12") (pin "2") (pinfunction "E_2") (pintype "passive"))
      (node (ref "Q13") (pin "2") (pinfunction "E_2") (pintype "passive"))
      (node (ref "Q14") (pin "2") (pinfunction "E_2") (pintype "passive"))
      (node (ref "Q15") (pin "2") (pinfunction "E_2") (pintype "passive"))
      (node (ref "Q16") (pin "2") (pinfunction "E_2") (pintype "passive"))
      (node (ref "Q17") (pin "2") (pinfunction "E_2") (pintype "passive"))
      (node (ref "Q18") (pin "2") (pinfunction "E_2") (pintype "passive"))
      (node (ref "Q19") (pin "2") (pinfunction "E_2") (pintype "passive"))
      (node (ref "Q2") (pin "2") (pinfunction "E_2") (pintype "passive"))
      (node (ref "Q20") (pin "2") (pinfunction "E_2") (pintype "passive"))
      (node (ref "Q21") (pin "2") (pinfunction "E_2") (pintype "passive"))
      (node (ref "Q22") (pin "2") (pinfunction "E_2") (pintype "passive"))
      (node (ref "Q23") (pin "2") (pinfunction "E_2") (pintype "passive"))
      (node (ref "Q24") (pin "2") (pinfunction "E_2") (pintype "passive"))
      (node (ref "Q25") (pin "2") (pinfunction "E_2") (pintype "passive"))
      (node (ref "Q26") (pin "2") (pinfunction "E_2") (pintype "passive"))
      (node (ref "Q27") (pin "2") (pinfunction "E_2") (pintype "passive"))
      (node (ref "Q28") (pin "2") (pinfunction "E_2") (pintype "passive"))
      (node (ref "Q29") (pin "2") (pinfunction "E_2") (pintype "passive"))
      (node (ref "Q3") (pin "2") (pinfunction "E_2") (pintype "passive"))
      (node (ref "Q30") (pin "2") (pinfunction "E_2") (pintype "passive"))
      (node (ref "Q31") (pin "2") (pinfunction "E_2") (pintype "passive"))
      (node (ref "Q32") (pin "2") (pinfunction "E_2") (pintype "passive"))
      (node (ref "Q4") (pin "2") (pinfunction "E_2") (pintype "passive"))
      (node (ref "Q5") (pin "2") (pinfunction "E_2") (pintype "passive"))
      (node (ref "Q6") (pin "2") (pinfunction "E_2") (pintype "passive"))
      (node (ref "Q7") (pin "2") (pinfunction "E_2") (pintype "passive"))
      (node (ref "Q8") (pin "2") (pinfunction "E_2") (pintype "passive"))
      (node (ref "Q9") (pin "2") (pinfunction "E_2") (pintype "passive"))
      (node (ref "R10") (pin "1") (pinfunction "1_1") (pintype "passive"))
      (node (ref "R11") (pin "1") (pinfunction "1_1") (pintype "passive"))
      (node (ref "R12") (pin "1") (pinfunction "1_1") (pintype "passive"))
      (node (ref "R13") (pin "1") (pinfunction "1_1") (pintype "passive"))
      (node (ref "R14") (pin "1") (pinfunction "1_1") (pintype "passive"))
      (node (ref "R15") (pin "1") (pinfunction "1_1") (pintype "passive"))
      (node (ref "R16") (pin "1") (pinfunction "1_1") (pintype "passive"))
      (node (ref "R33") (pin "1") (pinfunction "1_1") (pintype "passive"))
      (node (ref "R34") (pin "1") (pinfunction "1_1") (pintype "passive"))
      (node (ref "R35") (pin "1") (pinfunction "1_1") (pintype "passive"))
      (node (ref "R36") (pin "1") (pinfunction "1_1") (pintype "passive"))
      (node (ref "R37") (pin "1") (pinfunction "1_1") (pintype "passive"))
      (node (ref "R38") (pin "1") (pinfunction "1_1") (pintype "passive"))
      (node (ref "R39") (pin "1") (pinfunction "1_1") (pintype "passive"))
      (node (ref "R40") (pin "1") (pinfunction "1_1") (pintype "passive"))
      (node (ref "R57") (pin "1") (pinfunction "1_1") (pintype "passive"))
      (node (ref "R58") (pin "1") (pinfunction "1_1") (pintype "passive"))
      (node (ref "R59") (pin "1") (pinfunction "1_1") (pintype "passive"))
      (node (ref "R60") (pin "1") (pinfunction "1_1") (pintype "passive"))
      (node (ref "R61") (pin "1") (pinfunction "1_1") (pintype "passive"))
      (node (ref "R62") (pin "1") (pinfunction "1_1") (pintype "passive"))
      (node (ref "R63") (pin "1") (pinfunction "1_1") (pintype "passive"))
      (node (ref "R64") (pin "1") (pinfunction "1_1") (pintype "passive"))
      (node (ref "R81") (pin "1") (pinfunction "1_1") (pintype "passive"))
      (node (ref "R82") (pin "1") (pinfunction "1_1") (pintype "passive"))
      (node (ref "R83") (pin "1") (pinfunction "1_1") (pintype "passive"))
      (node (ref "R84") (pin "1") (pinfunction "1_1") (pintype "passive"))
      (node (ref "R85") (pin "1") (pinfunction "1_1") (pintype "passive"))
      (node (ref "R86") (pin "1") (pinfunction "1_1") (pintype "passive"))
      (node (ref "R87") (pin "1") (pinfunction "1_1") (pintype "passive"))
      (node (ref "R88") (pin "1") (pinfunction "1_1") (pintype "passive"))
    )
    (net (code "128") (name "unconnected-(R25-Pad1)") (class "Default")
      (node (ref "R25") (pin "1") (pinfunction "1_1") (pintype "passive"))
    )
  )
)
